# xiao_rp2040_round_lcd.net
KiCad netlist of a schematic drawn in EAGLE
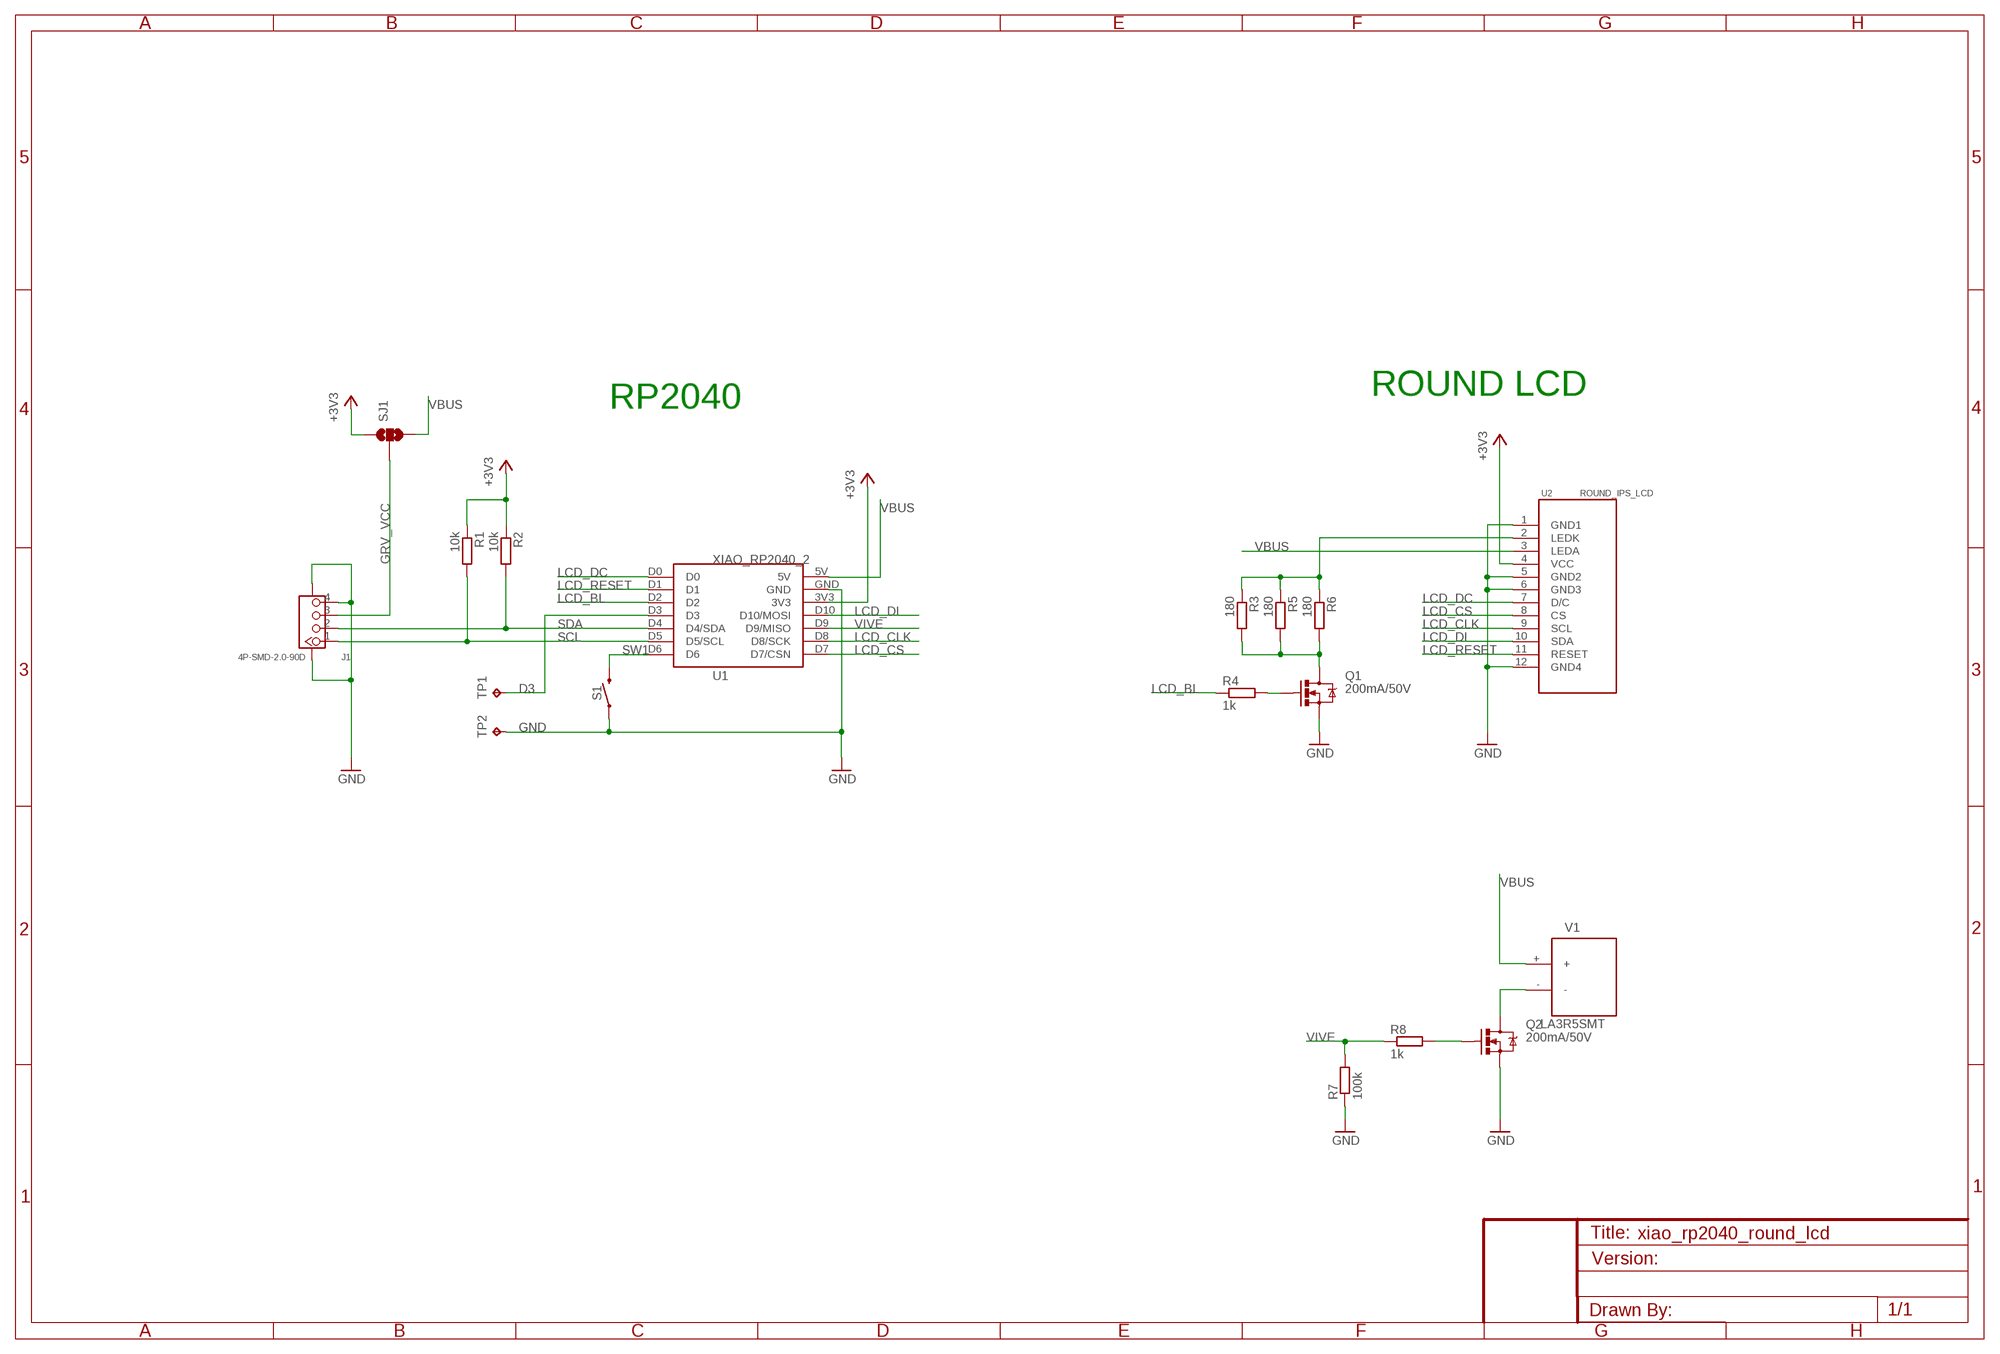
[diagram p0: schematic, sheet 1]

(export (version "E")
  (design (tool "Eeschema 10.0.6"))
  (components
    (comp (ref "J1")
      (value "4P-SMD-2.0-90D")
      (footprint "eagle-import:HW4-SMD-2.0-90D")
      (libsource (lib "eagle-import") (part "GROVE-CONNECTOR-SMD-90D(4+2P-2.0)"))
    )
    (comp (ref "Q1")
      (value "200mA/50V")
      (footprint "eagle-import:SOT23-3")
      (libsource (lib "eagle-import") (part "MOSFET-NCHANNELBSS138"))
    )
    (comp (ref "Q2")
      (value "200mA/50V")
      (footprint "eagle-import:SOT23-3")
      (libsource (lib "eagle-import") (part "MOSFET-NCHANNELBSS138"))
    )
    (comp (ref "R1")
      (value "10k")
      (footprint "eagle-import:R0603")
      (libsource (lib "eagle-import") (part "R-EU_R0603"))
    )
    (comp (ref "R2")
      (value "10k")
      (footprint "eagle-import:R0603")
      (libsource (lib "eagle-import") (part "R-EU_R0603"))
    )
    (comp (ref "R3")
      (value "180")
      (footprint "eagle-import:R0603")
      (libsource (lib "eagle-import") (part "R-EU_R0603"))
    )
    (comp (ref "R4")
      (value "1k")
      (footprint "eagle-import:R0603")
      (libsource (lib "eagle-import") (part "R-EU_R0603"))
    )
    (comp (ref "R5")
      (value "180")
      (footprint "eagle-import:R0603")
      (libsource (lib "eagle-import") (part "R-EU_R0603"))
    )
    (comp (ref "R6")
      (value "180")
      (footprint "eagle-import:R0603")
      (libsource (lib "eagle-import") (part "R-EU_R0603"))
    )
    (comp (ref "R7")
      (value "100k")
      (footprint "eagle-import:R0603")
      (libsource (lib "eagle-import") (part "R-EU_R0603"))
    )
    (comp (ref "R8")
      (value "1k")
      (footprint "eagle-import:R0603")
      (libsource (lib "eagle-import") (part "R-EU_R0603"))
    )
    (comp (ref "S1")
      (value "TACT_SW_3X4")
      (footprint "eagle-import:TACTILE_SWITCH_SMD_3X4MM")
      (libsource (lib "eagle-import") (part "TACT_SW_3X4"))
    )
    (comp (ref "SJ1")
      (value "SOLDERJUMPER_2WAYS")
      (footprint "eagle-import:SJ_3")
      (libsource (lib "eagle-import") (part "SOLDERJUMPER_2WAYS"))
    )
    (comp (ref "TP1")
      (value "TPTP18R")
      (footprint "eagle-import:TP18R")
      (libsource (lib "eagle-import") (part "TPTP18R"))
    )
    (comp (ref "TP2")
      (value "TPTP18R")
      (footprint "eagle-import:TP18R")
      (libsource (lib "eagle-import") (part "TPTP18R"))
    )
    (comp (ref "U1")
      (value "XIAO_RP2040_2")
      (footprint "eagle-import:XIAO_RP2040_2")
      (libsource (lib "eagle-import") (part "XIAO_RP2040_2"))
    )
    (comp (ref "U2")
      (value "ROUND_IPS_LCD")
      (footprint "eagle-import:ROUND_IPS_LCD")
      (libsource (lib "eagle-import") (part "ROUND_IPS_LCD"))
    )
    (comp (ref "V1")
      (value "LA3R5SMT")
      (footprint "eagle-import:LA3R5-2")
      (libsource (lib "eagle-import") (part "LA3R5SMT"))
    )
  )
  (nets
    (net (code "1") (name "+3V3") (class "Default")
      (node (ref "R1") (pin "1") (pinfunction "1_1") (pintype "passive"))
      (node (ref "R2") (pin "1") (pinfunction "1_1") (pintype "passive"))
      (node (ref "SJ1") (pin "1") (pinfunction "1_1") (pintype "passive"))
      (node (ref "U1") (pin "3V3") (pinfunction "3V3_3V3") (pintype "power_in"))
      (node (ref "U2") (pin "4") (pinfunction "VCC_4") (pintype "power_in"))
    )
    (net (code "2") (name "/D3") (class "Default")
      (node (ref "TP1") (pin "TP") (pinfunction "TP_TP") (pintype "input"))
      (node (ref "U1") (pin "D3") (pinfunction "D3_D3") (pintype "bidirectional"))
    )
    (net (code "3") (name "/GRV_VCC") (class "Default")
      (node (ref "J1") (pin "3") (pinfunction "3_3") (pintype "bidirectional"))
      (node (ref "SJ1") (pin "2") (pinfunction "2_2") (pintype "passive"))
    )
    (net (code "4") (name "/LCD_BL") (class "Default")
      (node (ref "R4") (pin "1") (pinfunction "1_1") (pintype "passive"))
      (node (ref "U1") (pin "D2") (pinfunction "D2_D2") (pintype "bidirectional"))
    )
    (net (code "5") (name "/LCD_CLK") (class "Default")
      (node (ref "U1") (pin "D8") (pinfunction "D8/SCK_D8") (pintype "bidirectional"))
      (node (ref "U2") (pin "9") (pinfunction "SCL_9") (pintype "input"))
    )
    (net (code "6") (name "/LCD_CS") (class "Default")
      (node (ref "U1") (pin "D7") (pinfunction "D7/CSN_D7") (pintype "bidirectional"))
      (node (ref "U2") (pin "8") (pinfunction "CS_8") (pintype "input"))
    )
    (net (code "7") (name "/LCD_DC") (class "Default")
      (node (ref "U1") (pin "D0") (pinfunction "D0_D0") (pintype "bidirectional"))
      (node (ref "U2") (pin "7") (pinfunction "D/C_7") (pintype "input"))
    )
    (net (code "8") (name "/LCD_DI") (class "Default")
      (node (ref "U1") (pin "D10") (pinfunction "D10/MOSI_D10") (pintype "bidirectional"))
      (node (ref "U2") (pin "10") (pinfunction "SDA_10") (pintype "bidirectional"))
    )
    (net (code "9") (name "/LCD_RESET") (class "Default")
      (node (ref "U1") (pin "D1") (pinfunction "D1_D1") (pintype "bidirectional"))
      (node (ref "U2") (pin "11") (pinfunction "RESET_11") (pintype "input"))
    )
    (net (code "10") (name "/SCL") (class "Default")
      (node (ref "J1") (pin "1") (pinfunction "1_1") (pintype "bidirectional"))
      (node (ref "R1") (pin "2") (pinfunction "2_2") (pintype "passive"))
      (node (ref "U1") (pin "D5") (pinfunction "D5/SCL_D5") (pintype "bidirectional"))
    )
    (net (code "11") (name "/SDA") (class "Default")
      (node (ref "J1") (pin "2") (pinfunction "2_2") (pintype "bidirectional"))
      (node (ref "R2") (pin "2") (pinfunction "2_2") (pintype "passive"))
      (node (ref "U1") (pin "D4") (pinfunction "D4/SDA_D4") (pintype "bidirectional"))
    )
    (net (code "12") (name "/SW1") (class "Default")
      (node (ref "S1") (pin "3") (pinfunction "2_3") (pintype "passive"))
      (node (ref "S1") (pin "4") (pinfunction "2_4") (pintype "passive"))
      (node (ref "U1") (pin "D6") (pinfunction "D6_D6") (pintype "bidirectional"))
    )
    (net (code "13") (name "/VBUS") (class "Default")
      (node (ref "SJ1") (pin "3") (pinfunction "3_3") (pintype "passive"))
      (node (ref "U1") (pin "5V") (pinfunction "5V_5V") (pintype "bidirectional"))
      (node (ref "U2") (pin "3") (pinfunction "LEDA_3") (pintype "bidirectional"))
      (node (ref "V1") (pin "+") (pinfunction "+_+") (pintype "bidirectional"))
    )
    (net (code "14") (name "/VIVE") (class "Default")
      (node (ref "R7") (pin "2") (pinfunction "2_2") (pintype "passive"))
      (node (ref "R8") (pin "1") (pinfunction "1_1") (pintype "passive"))
      (node (ref "U1") (pin "D9") (pinfunction "D9/MISO_D9") (pintype "bidirectional"))
    )
    (net (code "15") (name "GND") (class "Default")
      (node (ref "J1") (pin "4") (pinfunction "4_4") (pintype "bidirectional"))
      (node (ref "J1") (pin "SS1") (pinfunction "SS1_SS1") (pintype "bidirectional"))
      (node (ref "J1") (pin "SS2") (pinfunction "SS2_SS2") (pintype "bidirectional"))
      (node (ref "Q1") (pin "2") (pinfunction "S_2") (pintype "passive"))
      (node (ref "Q2") (pin "2") (pinfunction "S_2") (pintype "passive"))
      (node (ref "R7") (pin "1") (pinfunction "1_1") (pintype "passive"))
      (node (ref "S1") (pin "1") (pinfunction "1_1") (pintype "passive"))
      (node (ref "S1") (pin "2") (pinfunction "1_2") (pintype "passive"))
      (node (ref "TP2") (pin "TP") (pinfunction "TP_TP") (pintype "input"))
      (node (ref "U1") (pin "GND") (pinfunction "GND_GND") (pintype "power_in"))
      (node (ref "U2") (pin "1") (pinfunction "GND1_1") (pintype "power_in"))
      (node (ref "U2") (pin "12") (pinfunction "GND4_12") (pintype "power_in"))
      (node (ref "U2") (pin "5") (pinfunction "GND2_5") (pintype "power_in"))
      (node (ref "U2") (pin "6") (pinfunction "GND3_6") (pintype "power_in"))
    )
    (net (code "16") (name "Net-(Q1-D)") (class "Default")
      (node (ref "Q1") (pin "3") (pinfunction "D_3") (pintype "passive"))
      (node (ref "R3") (pin "2") (pinfunction "2_2") (pintype "passive"))
      (node (ref "R5") (pin "2") (pinfunction "2_2") (pintype "passive"))
      (node (ref "R6") (pin "2") (pinfunction "2_2") (pintype "passive"))
    )
    (net (code "17") (name "Net-(Q1-G)") (class "Default")
      (node (ref "Q1") (pin "1") (pinfunction "G_1") (pintype "passive"))
      (node (ref "R4") (pin "2") (pinfunction "2_2") (pintype "passive"))
    )
    (net (code "18") (name "Net-(Q2-D)") (class "Default")
      (node (ref "Q2") (pin "3") (pinfunction "D_3") (pintype "passive"))
      (node (ref "V1") (pin "-") (pinfunction "-_-") (pintype "bidirectional"))
    )
    (net (code "19") (name "Net-(Q2-G)") (class "Default")
      (node (ref "Q2") (pin "1") (pinfunction "G_1") (pintype "passive"))
      (node (ref "R8") (pin "2") (pinfunction "2_2") (pintype "passive"))
    )
    (net (code "20") (name "Net-(U2-LEDK)") (class "Default")
      (node (ref "R3") (pin "1") (pinfunction "1_1") (pintype "passive"))
      (node (ref "R5") (pin "1") (pinfunction "1_1") (pintype "passive"))
      (node (ref "R6") (pin "1") (pinfunction "1_1") (pintype "passive"))
      (node (ref "U2") (pin "2") (pinfunction "LEDK_2") (pintype "bidirectional"))
    )
  )
)
